# Platine.net
KiCad netlist of a schematic drawn in EAGLE
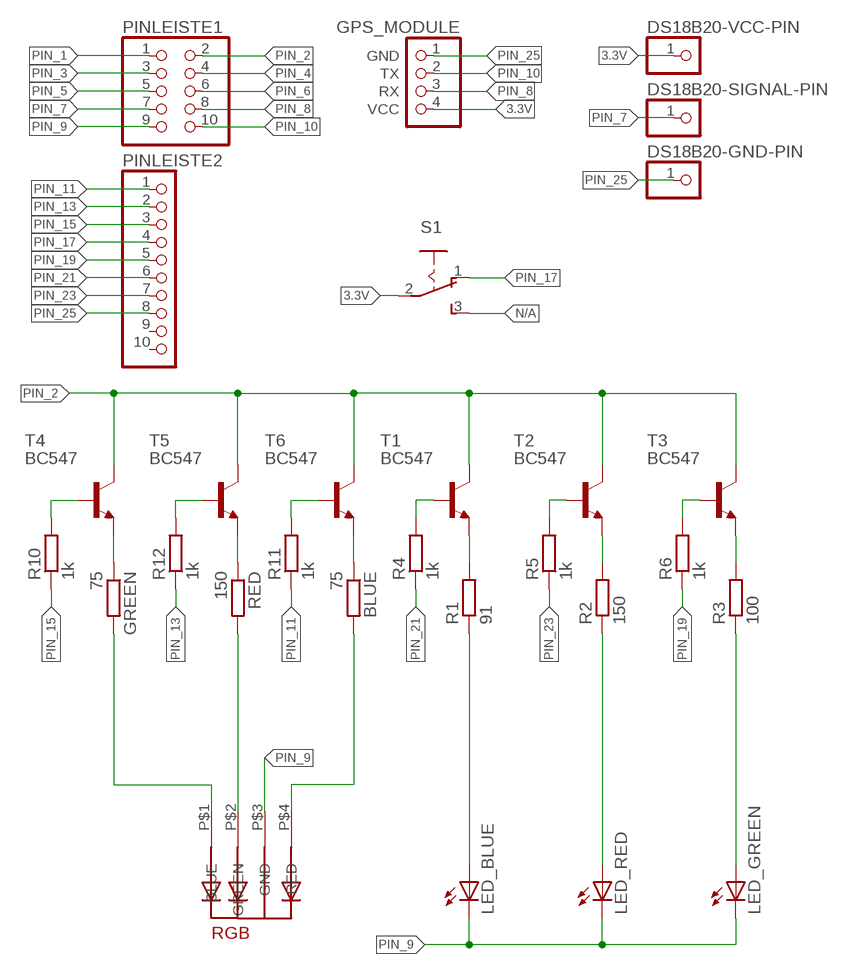
[diagram p0: schematic, sheet 1]

(export (version "E")
  (design (tool "Eeschema 10.0.6"))
  (components
    (comp (ref "BLUE")
      (value "75")
      (footprint "eagle-import:0207_10")
      (libsource (lib "eagle-import") (part "R-EU_0207/10"))
    )
    (comp (ref "DS18B20-GND-PIN")
      (value "PINHD-1X1")
      (footprint "eagle-import:1X01")
      (libsource (lib "eagle-import") (part "PINHD-1X1"))
    )
    (comp (ref "DS18B20-SIGNAL-PIN")
      (value "PINHD-1X1")
      (footprint "eagle-import:1X01")
      (libsource (lib "eagle-import") (part "PINHD-1X1"))
    )
    (comp (ref "DS18B20-VCC-PIN")
      (value "PINHD-1X1")
      (footprint "eagle-import:1X01")
      (libsource (lib "eagle-import") (part "PINHD-1X1"))
    )
    (comp (ref "GPS_MODULE")
      (value "PINHD-1X4")
      (footprint "eagle-import:1X04")
      (libsource (lib "eagle-import") (part "PINHD-1X4"))
    )
    (comp (ref "GREEN")
      (value "75")
      (footprint "eagle-import:0207_10")
      (libsource (lib "eagle-import") (part "R-EU_0207/10"))
    )
    (comp (ref "LED_BLUE")
      (value "LED5MM")
      (footprint "eagle-import:LED5MM")
      (libsource (lib "eagle-import") (part "LED5MM"))
    )
    (comp (ref "LED_GREEN")
      (value "LED5MM")
      (footprint "eagle-import:LED5MM")
      (libsource (lib "eagle-import") (part "LED5MM"))
    )
    (comp (ref "LED_RED")
      (value "LED5MM")
      (footprint "eagle-import:LED5MM")
      (libsource (lib "eagle-import") (part "LED5MM"))
    )
    (comp (ref "PINLEISTE1")
      (value "PINHD-2X5")
      (footprint "eagle-import:2X05")
      (libsource (lib "eagle-import") (part "PINHD-2X5"))
    )
    (comp (ref "PINLEISTE2")
      (value "PINHD-1X10")
      (footprint "eagle-import:1X10")
      (libsource (lib "eagle-import") (part "PINHD-1X10"))
    )
    (comp (ref "R1")
      (value "91")
      (footprint "eagle-import:0207_10")
      (libsource (lib "eagle-import") (part "R-EU_0207/10"))
    )
    (comp (ref "R2")
      (value "150")
      (footprint "eagle-import:0207_10")
      (libsource (lib "eagle-import") (part "R-EU_0207/10"))
    )
    (comp (ref "R3")
      (value "100")
      (footprint "eagle-import:0207_10")
      (libsource (lib "eagle-import") (part "R-EU_0207/10"))
    )
    (comp (ref "R4")
      (value "1k")
      (footprint "eagle-import:0207_10")
      (libsource (lib "eagle-import") (part "R-EU_0207/10"))
    )
    (comp (ref "R5")
      (value "1k")
      (footprint "eagle-import:0207_10")
      (libsource (lib "eagle-import") (part "R-EU_0207/10"))
    )
    (comp (ref "R6")
      (value "1k")
      (footprint "eagle-import:0207_10")
      (libsource (lib "eagle-import") (part "R-EU_0207/10"))
    )
    (comp (ref "R10")
      (value "1k")
      (footprint "eagle-import:0207_10")
      (libsource (lib "eagle-import") (part "R-EU_0207/10"))
    )
    (comp (ref "R11")
      (value "1k")
      (footprint "eagle-import:0207_10")
      (libsource (lib "eagle-import") (part "R-EU_0207/10"))
    )
    (comp (ref "R12")
      (value "1k")
      (footprint "eagle-import:0207_10")
      (libsource (lib "eagle-import") (part "R-EU_0207/10"))
    )
    (comp (ref "RED")
      (value "150")
      (footprint "eagle-import:0207_10")
      (libsource (lib "eagle-import") (part "R-EU_0207/10"))
    )
    (comp (ref "RGB")
      (value "5MMRGBLED")
      (footprint "eagle-import:LED5MMRGB")
      (libsource (lib "eagle-import") (part "5MMRGBLED"))
    )
    (comp (ref "S1")
      (value "255SB")
      (footprint "eagle-import:255SB")
      (libsource (lib "eagle-import") (part "255SB"))
    )
    (comp (ref "T1")
      (value "BC547")
      (footprint "eagle-import:TO92")
      (libsource (lib "eagle-import") (part "BC547"))
    )
    (comp (ref "T2")
      (value "BC547")
      (footprint "eagle-import:TO92")
      (libsource (lib "eagle-import") (part "BC547"))
    )
    (comp (ref "T3")
      (value "BC547")
      (footprint "eagle-import:TO92")
      (libsource (lib "eagle-import") (part "BC547"))
    )
    (comp (ref "T4")
      (value "BC547")
      (footprint "eagle-import:TO92")
      (libsource (lib "eagle-import") (part "BC547"))
    )
    (comp (ref "T5")
      (value "BC547")
      (footprint "eagle-import:TO92")
      (libsource (lib "eagle-import") (part "BC547"))
    )
    (comp (ref "T6")
      (value "BC547")
      (footprint "eagle-import:TO92")
      (libsource (lib "eagle-import") (part "BC547"))
    )
  )
  (nets
    (net (code "1") (name "3.3V") (class "Default")
      (node (ref "DS18B20-VCC-PIN") (pin "1") (pinfunction "1_1") (pintype "passive"))
      (node (ref "GPS_MODULE") (pin "4") (pinfunction "VCC_4") (pintype "passive"))
      (node (ref "S1") (pin "2") (pinfunction "P_2") (pintype "passive"))
    )
    (net (code "2") (name "Net-(LED_BLUE-PadA)") (class "Default")
      (node (ref "LED_BLUE") (pin "A") (pinfunction "A_A") (pintype "passive"))
      (node (ref "R1") (pin "1") (pinfunction "1_1") (pintype "passive"))
    )
    (net (code "3") (name "Net-(LED_GREEN-PadA)") (class "Default")
      (node (ref "LED_GREEN") (pin "A") (pinfunction "A_A") (pintype "passive"))
      (node (ref "R3") (pin "1") (pinfunction "1_1") (pintype "passive"))
    )
    (net (code "4") (name "Net-(LED_RED-PadA)") (class "Default")
      (node (ref "LED_RED") (pin "A") (pinfunction "A_A") (pintype "passive"))
      (node (ref "R2") (pin "1") (pinfunction "1_1") (pintype "passive"))
    )
    (net (code "5") (name "Net-(RGB-BLUE)") (class "Default")
      (node (ref "GREEN") (pin "2") (pinfunction "2_2") (pintype "passive"))
      (node (ref "RGB") (pin "P$1") (pinfunction "BLUE_P$1") (pintype "bidirectional"))
    )
    (net (code "6") (name "Net-(RGB-GREEN)") (class "Default")
      (node (ref "RED") (pin "2") (pinfunction "2_2") (pintype "passive"))
      (node (ref "RGB") (pin "P$2") (pinfunction "GREEN_P$2") (pintype "bidirectional"))
    )
    (net (code "7") (name "Net-(RGB-RED)") (class "Default")
      (node (ref "BLUE") (pin "2") (pinfunction "2_2") (pintype "passive"))
      (node (ref "RGB") (pin "P$4") (pinfunction "RED_P$4") (pintype "bidirectional"))
    )
    (net (code "8") (name "Net-(T1-B)") (class "Default")
      (node (ref "R4") (pin "2") (pinfunction "2_2") (pintype "passive"))
      (node (ref "T1") (pin "2") (pinfunction "B_2") (pintype "passive"))
    )
    (net (code "9") (name "Net-(T1-E)") (class "Default")
      (node (ref "R1") (pin "2") (pinfunction "2_2") (pintype "passive"))
      (node (ref "T1") (pin "1") (pinfunction "E_1") (pintype "passive"))
    )
    (net (code "10") (name "Net-(T2-B)") (class "Default")
      (node (ref "R5") (pin "2") (pinfunction "2_2") (pintype "passive"))
      (node (ref "T2") (pin "2") (pinfunction "B_2") (pintype "passive"))
    )
    (net (code "11") (name "Net-(T2-E)") (class "Default")
      (node (ref "R2") (pin "2") (pinfunction "2_2") (pintype "passive"))
      (node (ref "T2") (pin "1") (pinfunction "E_1") (pintype "passive"))
    )
    (net (code "12") (name "Net-(T3-B)") (class "Default")
      (node (ref "R6") (pin "2") (pinfunction "2_2") (pintype "passive"))
      (node (ref "T3") (pin "2") (pinfunction "B_2") (pintype "passive"))
    )
    (net (code "13") (name "Net-(T3-E)") (class "Default")
      (node (ref "R3") (pin "2") (pinfunction "2_2") (pintype "passive"))
      (node (ref "T3") (pin "1") (pinfunction "E_1") (pintype "passive"))
    )
    (net (code "14") (name "Net-(T4-B)") (class "Default")
      (node (ref "R10") (pin "2") (pinfunction "2_2") (pintype "passive"))
      (node (ref "T4") (pin "2") (pinfunction "B_2") (pintype "passive"))
    )
    (net (code "15") (name "Net-(T4-E)") (class "Default")
      (node (ref "GREEN") (pin "1") (pinfunction "1_1") (pintype "passive"))
      (node (ref "T4") (pin "1") (pinfunction "E_1") (pintype "passive"))
    )
    (net (code "16") (name "Net-(T5-B)") (class "Default")
      (node (ref "R12") (pin "2") (pinfunction "2_2") (pintype "passive"))
      (node (ref "T5") (pin "2") (pinfunction "B_2") (pintype "passive"))
    )
    (net (code "17") (name "Net-(T5-E)") (class "Default")
      (node (ref "RED") (pin "1") (pinfunction "1_1") (pintype "passive"))
      (node (ref "T5") (pin "1") (pinfunction "E_1") (pintype "passive"))
    )
    (net (code "18") (name "Net-(T6-B)") (class "Default")
      (node (ref "R11") (pin "2") (pinfunction "2_2") (pintype "passive"))
      (node (ref "T6") (pin "2") (pinfunction "B_2") (pintype "passive"))
    )
    (net (code "19") (name "Net-(T6-E)") (class "Default")
      (node (ref "BLUE") (pin "1") (pinfunction "1_1") (pintype "passive"))
      (node (ref "T6") (pin "1") (pinfunction "E_1") (pintype "passive"))
    )
    (net (code "20") (name "N{slash}A") (class "Default")
      (node (ref "S1") (pin "3") (pinfunction "S_3") (pintype "passive"))
    )
    (net (code "21") (name "PIN_1") (class "Default")
      (node (ref "PINLEISTE1") (pin "1") (pinfunction "1_1") (pintype "passive"))
    )
    (net (code "22") (name "PIN_2") (class "Default")
      (node (ref "PINLEISTE1") (pin "2") (pinfunction "2_2") (pintype "passive"))
      (node (ref "T1") (pin "3") (pinfunction "C_3") (pintype "passive"))
      (node (ref "T2") (pin "3") (pinfunction "C_3") (pintype "passive"))
      (node (ref "T3") (pin "3") (pinfunction "C_3") (pintype "passive"))
      (node (ref "T4") (pin "3") (pinfunction "C_3") (pintype "passive"))
      (node (ref "T5") (pin "3") (pinfunction "C_3") (pintype "passive"))
      (node (ref "T6") (pin "3") (pinfunction "C_3") (pintype "passive"))
    )
    (net (code "23") (name "PIN_3") (class "Default")
      (node (ref "PINLEISTE1") (pin "3") (pinfunction "3_3") (pintype "passive"))
    )
    (net (code "24") (name "PIN_4") (class "Default")
      (node (ref "PINLEISTE1") (pin "4") (pinfunction "4_4") (pintype "passive"))
    )
    (net (code "25") (name "PIN_5") (class "Default")
      (node (ref "PINLEISTE1") (pin "5") (pinfunction "5_5") (pintype "passive"))
    )
    (net (code "26") (name "PIN_6") (class "Default")
      (node (ref "PINLEISTE1") (pin "6") (pinfunction "6_6") (pintype "passive"))
    )
    (net (code "27") (name "PIN_7") (class "Default")
      (node (ref "DS18B20-SIGNAL-PIN") (pin "1") (pinfunction "1_1") (pintype "passive"))
      (node (ref "PINLEISTE1") (pin "7") (pinfunction "7_7") (pintype "passive"))
    )
    (net (code "28") (name "PIN_8") (class "Default")
      (node (ref "GPS_MODULE") (pin "3") (pinfunction "RX_3") (pintype "passive"))
      (node (ref "PINLEISTE1") (pin "8") (pinfunction "8_8") (pintype "passive"))
    )
    (net (code "29") (name "PIN_9") (class "Default")
      (node (ref "LED_BLUE") (pin "K") (pinfunction "C_K") (pintype "passive"))
      (node (ref "LED_GREEN") (pin "K") (pinfunction "C_K") (pintype "passive"))
      (node (ref "LED_RED") (pin "K") (pinfunction "C_K") (pintype "passive"))
      (node (ref "PINLEISTE1") (pin "9") (pinfunction "9_9") (pintype "passive"))
      (node (ref "RGB") (pin "P$3") (pinfunction "GND_P$3") (pintype "bidirectional"))
    )
    (net (code "30") (name "PIN_10") (class "Default")
      (node (ref "GPS_MODULE") (pin "2") (pinfunction "TX_2") (pintype "passive"))
      (node (ref "PINLEISTE1") (pin "10") (pinfunction "10_10") (pintype "passive"))
    )
    (net (code "31") (name "PIN_11") (class "Default")
      (node (ref "PINLEISTE2") (pin "1") (pinfunction "1_1") (pintype "passive"))
      (node (ref "R11") (pin "1") (pinfunction "1_1") (pintype "passive"))
    )
    (net (code "32") (name "PIN_13") (class "Default")
      (node (ref "PINLEISTE2") (pin "2") (pinfunction "2_2") (pintype "passive"))
      (node (ref "R12") (pin "1") (pinfunction "1_1") (pintype "passive"))
    )
    (net (code "33") (name "PIN_15") (class "Default")
      (node (ref "PINLEISTE2") (pin "3") (pinfunction "3_3") (pintype "passive"))
      (node (ref "R10") (pin "1") (pinfunction "1_1") (pintype "passive"))
    )
    (net (code "34") (name "PIN_17") (class "Default")
      (node (ref "PINLEISTE2") (pin "4") (pinfunction "4_4") (pintype "passive"))
      (node (ref "S1") (pin "1") (pinfunction "O_1") (pintype "passive"))
    )
    (net (code "35") (name "PIN_19") (class "Default")
      (node (ref "PINLEISTE2") (pin "5") (pinfunction "5_5") (pintype "passive"))
      (node (ref "R6") (pin "1") (pinfunction "1_1") (pintype "passive"))
    )
    (net (code "36") (name "PIN_21") (class "Default")
      (node (ref "PINLEISTE2") (pin "6") (pinfunction "6_6") (pintype "passive"))
      (node (ref "R4") (pin "1") (pinfunction "1_1") (pintype "passive"))
    )
    (net (code "37") (name "PIN_23") (class "Default")
      (node (ref "PINLEISTE2") (pin "7") (pinfunction "7_7") (pintype "passive"))
      (node (ref "R5") (pin "1") (pinfunction "1_1") (pintype "passive"))
    )
    (net (code "38") (name "PIN_25") (class "Default")
      (node (ref "DS18B20-GND-PIN") (pin "1") (pinfunction "1_1") (pintype "passive"))
      (node (ref "GPS_MODULE") (pin "1") (pinfunction "GND_1") (pintype "passive"))
      (node (ref "PINLEISTE2") (pin "8") (pinfunction "8_8") (pintype "passive"))
    )
    (net (code "39") (name "unconnected-(PINLEISTE2-Pad9)") (class "Default")
      (node (ref "PINLEISTE2") (pin "9") (pinfunction "9_9") (pintype "passive"))
    )
    (net (code "40") (name "unconnected-(PINLEISTE2-Pad10)") (class "Default")
      (node (ref "PINLEISTE2") (pin "10") (pinfunction "10_10") (pintype "passive"))
    )
  )
)
